# MegaPlay_Hammond1593J.net
KiCad netlist of a schematic drawn in EAGLE
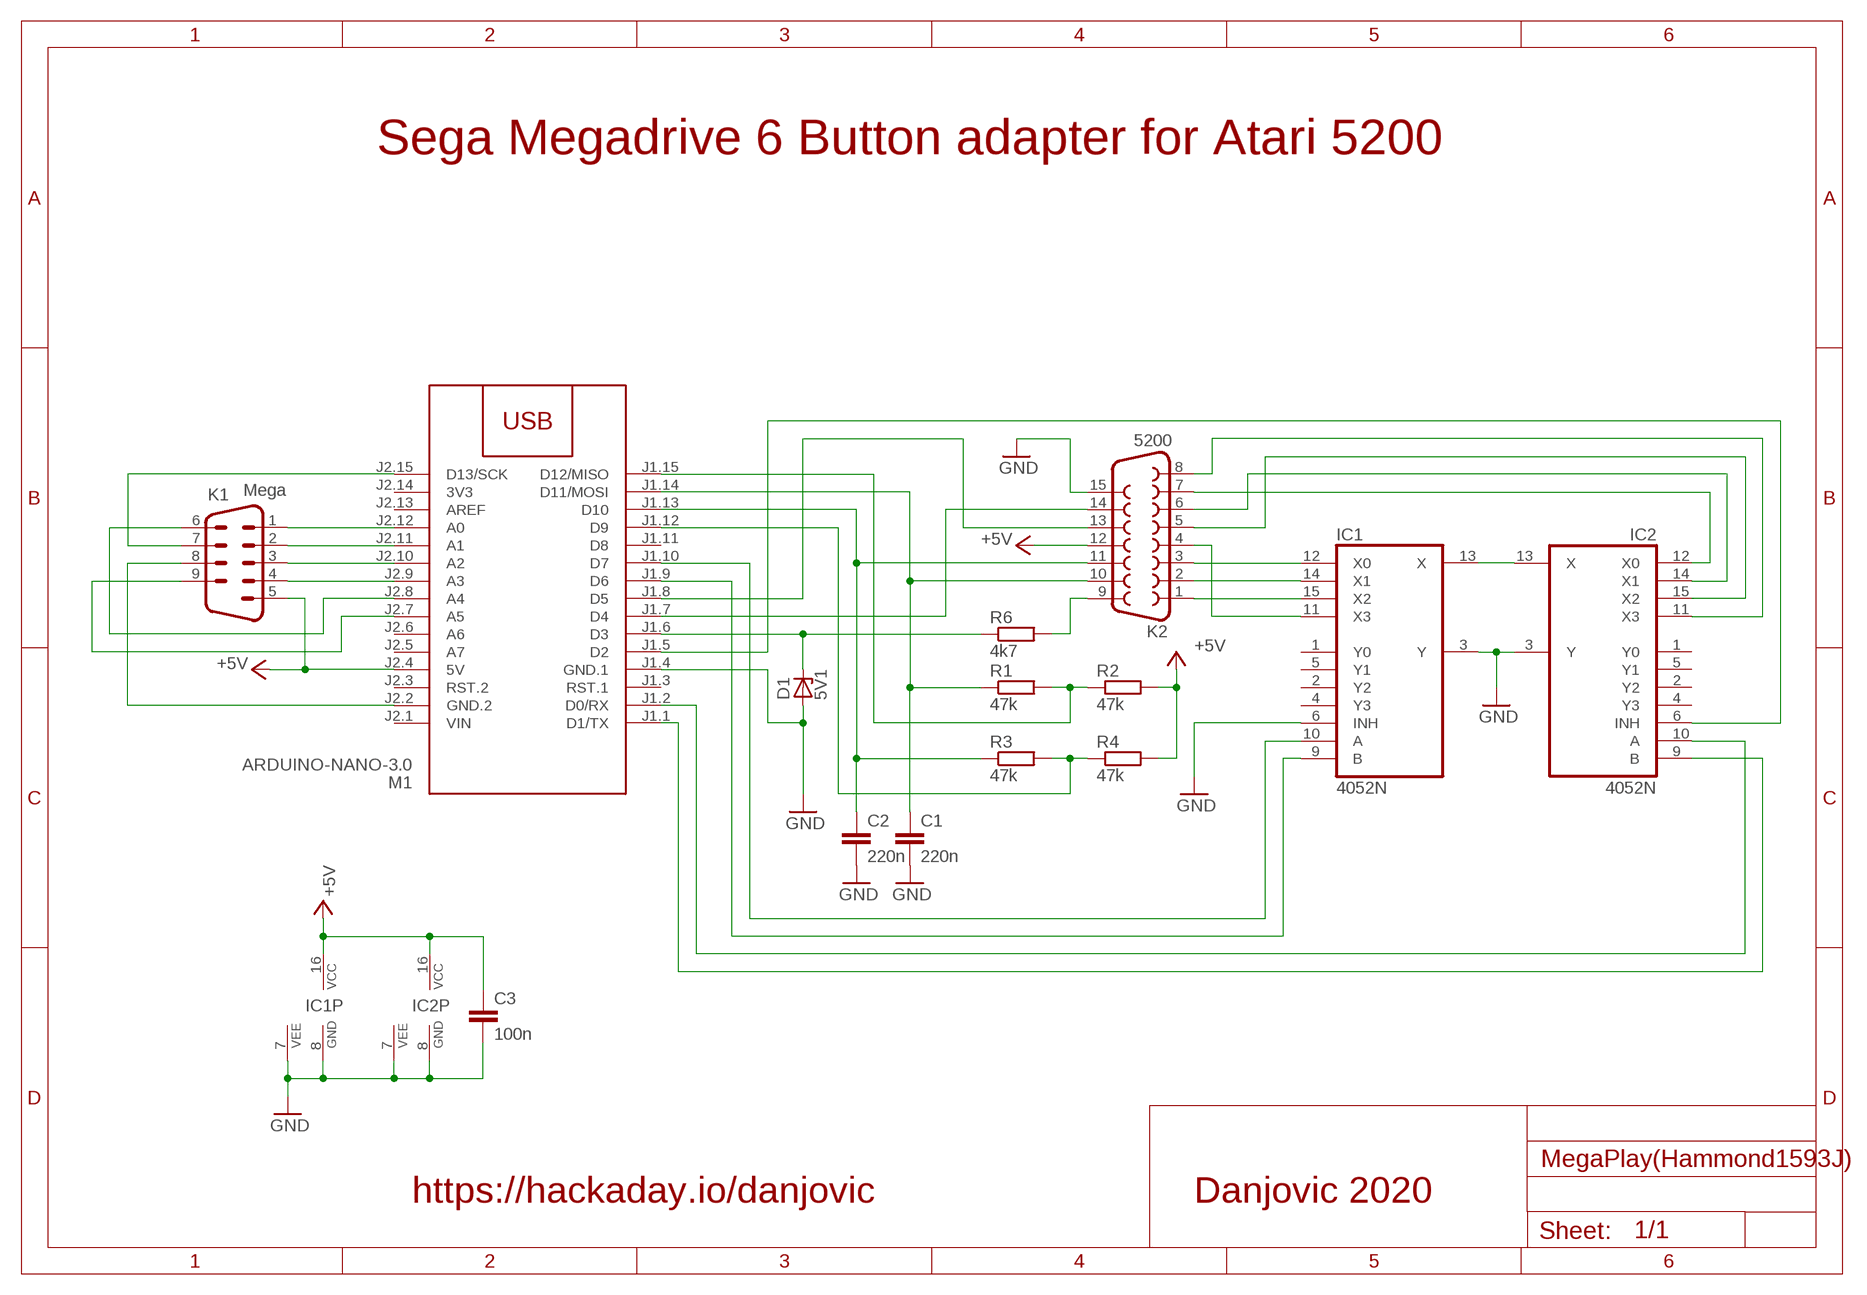
[diagram p0: schematic, sheet 1]

(export (version "E")
  (design (tool "Eeschema 10.0.6"))
  (components
    (comp (ref "C1")
      (value "220n")
      (footprint "eagle-import:C050-025X075")
      (libsource (lib "eagle-import") (part "C-EU050-025X075"))
    )
    (comp (ref "C2")
      (value "220n")
      (footprint "eagle-import:C050-025X075")
      (libsource (lib "eagle-import") (part "C-EU050-025X075"))
    )
    (comp (ref "C3")
      (value "100n")
      (footprint "eagle-import:C050-024X044")
      (libsource (lib "eagle-import") (part "C-EU050-024X044"))
    )
    (comp (ref "D1")
      (value "5V1")
      (footprint "eagle-import:ZDIO-7.5")
      (libsource (lib "eagle-import") (part "ZENER-DIODEZD-7.5"))
    )
    (comp (ref "IC1")
      (value "4052N")
      (footprint "eagle-import:DIL16")
      (libsource (lib "eagle-import") (part "4052N"))
    )
    (comp (ref "IC2")
      (value "4052N")
      (footprint "eagle-import:DIL16")
      (libsource (lib "eagle-import") (part "4052N"))
    )
    (comp (ref "K1")
      (value "Mega")
      (footprint "eagle-import:M09H")
      (libsource (lib "eagle-import") (part "M09H"))
    )
    (comp (ref "K2")
      (value "5200")
      (footprint "eagle-import:F15H")
      (libsource (lib "eagle-import") (part "F15H"))
    )
    (comp (ref "M1")
      (value "ARDUINO-NANO-3.0")
      (footprint "eagle-import:ARDUINO-NANO-3.0")
      (libsource (lib "eagle-import") (part "ARDUINO-NANO-3.0"))
    )
    (comp (ref "R1")
      (value "47k")
      (footprint "eagle-import:0204_7")
      (libsource (lib "eagle-import") (part "R-EU_0204/7"))
    )
    (comp (ref "R2")
      (value "47k")
      (footprint "eagle-import:0204_7")
      (libsource (lib "eagle-import") (part "R-EU_0204/7"))
    )
    (comp (ref "R3")
      (value "47k")
      (footprint "eagle-import:0204_7")
      (libsource (lib "eagle-import") (part "R-EU_0204/7"))
    )
    (comp (ref "R4")
      (value "47k")
      (footprint "eagle-import:0204_7")
      (libsource (lib "eagle-import") (part "R-EU_0204/7"))
    )
    (comp (ref "R6")
      (value "4k7")
      (footprint "eagle-import:0204_7")
      (libsource (lib "eagle-import") (part "R-EU_0204/7"))
    )
  )
  (nets
    (net (code "1") (name "+5V") (class "Default")
      (node (ref "C3") (pin "1") (pinfunction "1_1") (pintype "passive"))
      (node (ref "IC1") (pin "16") (pinfunction "VCC_16") (pintype "power_in"))
      (node (ref "IC2") (pin "16") (pinfunction "VCC_16") (pintype "power_in"))
      (node (ref "K1") (pin "5") (pinfunction "5_5") (pintype "passive"))
      (node (ref "K2") (pin "12") (pinfunction "12_12") (pintype "passive"))
      (node (ref "M1") (pin "J2.4") (pinfunction "5V_J2.4") (pintype "power_in"))
      (node (ref "R2") (pin "2") (pinfunction "2_2") (pintype "passive"))
      (node (ref "R4") (pin "2") (pinfunction "2_2") (pintype "passive"))
    )
    (net (code "2") (name "/3V3") (class "Default")
      (node (ref "M1") (pin "J2.14") (pinfunction "3V3_J2.14") (pintype "power_in"))
    )
    (net (code "3") (name "/VIN") (class "Default")
      (node (ref "M1") (pin "J2.1") (pinfunction "VIN_J2.1") (pintype "power_in"))
    )
    (net (code "4") (name "GND") (class "Default")
      (node (ref "C1") (pin "2") (pinfunction "2_2") (pintype "passive"))
      (node (ref "C2") (pin "2") (pinfunction "2_2") (pintype "passive"))
      (node (ref "C3") (pin "2") (pinfunction "2_2") (pintype "passive"))
      (node (ref "D1") (pin "A") (pinfunction "A_A") (pintype "passive"))
      (node (ref "IC1") (pin "3") (pinfunction "Y_3") (pintype "bidirectional"))
      (node (ref "IC1") (pin "6") (pinfunction "INH_6") (pintype "input"))
      (node (ref "IC1") (pin "7") (pinfunction "VEE_7") (pintype "power_in"))
      (node (ref "IC1") (pin "8") (pinfunction "GND_8") (pintype "power_in"))
      (node (ref "IC2") (pin "3") (pinfunction "Y_3") (pintype "bidirectional"))
      (node (ref "IC2") (pin "7") (pinfunction "VEE_7") (pintype "power_in"))
      (node (ref "IC2") (pin "8") (pinfunction "GND_8") (pintype "power_in"))
      (node (ref "K2") (pin "15") (pinfunction "15_15") (pintype "passive"))
      (node (ref "M1") (pin "J1.4") (pinfunction "GND.1_J1.4") (pintype "power_in"))
    )
    (net (code "5") (name "Net-(IC1A-A)") (class "Default")
      (node (ref "IC1") (pin "10") (pinfunction "A_10") (pintype "input"))
      (node (ref "M1") (pin "J1.10") (pinfunction "D7_J1.10") (pintype "bidirectional"))
    )
    (net (code "6") (name "Net-(IC1A-B)") (class "Default")
      (node (ref "IC1") (pin "9") (pinfunction "B_9") (pintype "input"))
      (node (ref "M1") (pin "J1.9") (pinfunction "D6_J1.9") (pintype "bidirectional"))
    )
    (net (code "7") (name "Net-(IC1A-X)") (class "Default")
      (node (ref "IC1") (pin "13") (pinfunction "X_13") (pintype "bidirectional"))
      (node (ref "IC2") (pin "13") (pinfunction "X_13") (pintype "bidirectional"))
    )
    (net (code "8") (name "Net-(IC1A-X0)") (class "Default")
      (node (ref "IC1") (pin "12") (pinfunction "X0_12") (pintype "bidirectional"))
      (node (ref "K2") (pin "3") (pinfunction "3_3") (pintype "passive"))
    )
    (net (code "9") (name "Net-(IC1A-X1)") (class "Default")
      (node (ref "IC1") (pin "14") (pinfunction "X1_14") (pintype "bidirectional"))
      (node (ref "K2") (pin "2") (pinfunction "2_2") (pintype "passive"))
    )
    (net (code "10") (name "Net-(IC1A-X2)") (class "Default")
      (node (ref "IC1") (pin "15") (pinfunction "X2_15") (pintype "bidirectional"))
      (node (ref "K2") (pin "1") (pinfunction "1_1") (pintype "passive"))
    )
    (net (code "11") (name "Net-(IC1A-X3)") (class "Default")
      (node (ref "IC1") (pin "11") (pinfunction "X3_11") (pintype "bidirectional"))
      (node (ref "K2") (pin "4") (pinfunction "4_4") (pintype "passive"))
    )
    (net (code "12") (name "Net-(IC2A-A)") (class "Default")
      (node (ref "IC2") (pin "10") (pinfunction "A_10") (pintype "input"))
      (node (ref "M1") (pin "J1.2") (pinfunction "D0/RX_J1.2") (pintype "bidirectional"))
    )
    (net (code "13") (name "Net-(IC2A-B)") (class "Default")
      (node (ref "IC2") (pin "9") (pinfunction "B_9") (pintype "input"))
      (node (ref "M1") (pin "J1.1") (pinfunction "D1/TX_J1.1") (pintype "bidirectional"))
    )
    (net (code "14") (name "Net-(IC2A-INH)") (class "Default")
      (node (ref "IC2") (pin "6") (pinfunction "INH_6") (pintype "input"))
      (node (ref "M1") (pin "J1.5") (pinfunction "D2_J1.5") (pintype "bidirectional"))
    )
    (net (code "15") (name "Net-(IC2A-X0)") (class "Default")
      (node (ref "IC2") (pin "12") (pinfunction "X0_12") (pintype "bidirectional"))
      (node (ref "K2") (pin "7") (pinfunction "7_7") (pintype "passive"))
    )
    (net (code "16") (name "Net-(IC2A-X1)") (class "Default")
      (node (ref "IC2") (pin "14") (pinfunction "X1_14") (pintype "bidirectional"))
      (node (ref "K2") (pin "6") (pinfunction "6_6") (pintype "passive"))
    )
    (net (code "17") (name "Net-(IC2A-X2)") (class "Default")
      (node (ref "IC2") (pin "15") (pinfunction "X2_15") (pintype "bidirectional"))
      (node (ref "K2") (pin "5") (pinfunction "5_5") (pintype "passive"))
    )
    (net (code "18") (name "Net-(IC2A-X3)") (class "Default")
      (node (ref "IC2") (pin "11") (pinfunction "X3_11") (pintype "bidirectional"))
      (node (ref "K2") (pin "8") (pinfunction "8_8") (pintype "passive"))
    )
    (net (code "19") (name "Net-(K2-Pad9)") (class "Default")
      (node (ref "K2") (pin "9") (pinfunction "9_9") (pintype "passive"))
      (node (ref "R6") (pin "2") (pinfunction "2_2") (pintype "passive"))
    )
    (net (code "20") (name "Net-(M1-A0)") (class "Default")
      (node (ref "K1") (pin "1") (pinfunction "1_1") (pintype "passive"))
      (node (ref "M1") (pin "J2.12") (pinfunction "A0_J2.12") (pintype "bidirectional"))
    )
    (net (code "21") (name "Net-(M1-A1)") (class "Default")
      (node (ref "K1") (pin "2") (pinfunction "2_2") (pintype "passive"))
      (node (ref "M1") (pin "J2.11") (pinfunction "A1_J2.11") (pintype "bidirectional"))
    )
    (net (code "22") (name "Net-(M1-A2)") (class "Default")
      (node (ref "K1") (pin "3") (pinfunction "3_3") (pintype "passive"))
      (node (ref "M1") (pin "J2.10") (pinfunction "A2_J2.10") (pintype "bidirectional"))
    )
    (net (code "23") (name "Net-(M1-A3)") (class "Default")
      (node (ref "K1") (pin "4") (pinfunction "4_4") (pintype "passive"))
      (node (ref "M1") (pin "J2.9") (pinfunction "A3_J2.9") (pintype "bidirectional"))
    )
    (net (code "24") (name "Net-(M1-A4)") (class "Default")
      (node (ref "K1") (pin "6") (pinfunction "6_6") (pintype "passive"))
      (node (ref "M1") (pin "J2.8") (pinfunction "A4_J2.8") (pintype "bidirectional"))
    )
    (net (code "25") (name "Net-(M1-A5)") (class "Default")
      (node (ref "K1") (pin "9") (pinfunction "9_9") (pintype "passive"))
      (node (ref "M1") (pin "J2.7") (pinfunction "A5_J2.7") (pintype "bidirectional"))
    )
    (net (code "26") (name "Net-(M1-D3)") (class "Default")
      (node (ref "D1") (pin "C") (pinfunction "C_C") (pintype "passive"))
      (node (ref "M1") (pin "J1.6") (pinfunction "D3_J1.6") (pintype "bidirectional"))
      (node (ref "R6") (pin "1") (pinfunction "1_1") (pintype "passive"))
    )
    (net (code "27") (name "Net-(M1-D4)") (class "Default")
      (node (ref "K2") (pin "14") (pinfunction "14_14") (pintype "passive"))
      (node (ref "M1") (pin "J1.7") (pinfunction "D4_J1.7") (pintype "bidirectional"))
    )
    (net (code "28") (name "Net-(M1-D5)") (class "Default")
      (node (ref "K2") (pin "13") (pinfunction "13_13") (pintype "passive"))
      (node (ref "M1") (pin "J1.8") (pinfunction "D5_J1.8") (pintype "bidirectional"))
    )
    (net (code "29") (name "Net-(M1-D9)") (class "Default")
      (node (ref "M1") (pin "J1.12") (pinfunction "D9_J1.12") (pintype "bidirectional"))
      (node (ref "R3") (pin "2") (pinfunction "2_2") (pintype "passive"))
      (node (ref "R4") (pin "1") (pinfunction "1_1") (pintype "passive"))
    )
    (net (code "30") (name "Net-(M1-D10)") (class "Default")
      (node (ref "C2") (pin "1") (pinfunction "1_1") (pintype "passive"))
      (node (ref "K2") (pin "11") (pinfunction "11_11") (pintype "passive"))
      (node (ref "M1") (pin "J1.13") (pinfunction "D10_J1.13") (pintype "bidirectional"))
      (node (ref "R3") (pin "1") (pinfunction "1_1") (pintype "passive"))
    )
    (net (code "31") (name "Net-(M1-D11{slash}MOSI)") (class "Default")
      (node (ref "C1") (pin "1") (pinfunction "1_1") (pintype "passive"))
      (node (ref "K2") (pin "10") (pinfunction "10_10") (pintype "passive"))
      (node (ref "M1") (pin "J1.14") (pinfunction "D11/MOSI_J1.14") (pintype "bidirectional"))
      (node (ref "R1") (pin "1") (pinfunction "1_1") (pintype "passive"))
    )
    (net (code "32") (name "Net-(M1-D12{slash}MISO)") (class "Default")
      (node (ref "M1") (pin "J1.15") (pinfunction "D12/MISO_J1.15") (pintype "bidirectional"))
      (node (ref "R1") (pin "2") (pinfunction "2_2") (pintype "passive"))
      (node (ref "R2") (pin "1") (pinfunction "1_1") (pintype "passive"))
    )
    (net (code "33") (name "Net-(M1-D13{slash}SCK)") (class "Default")
      (node (ref "K1") (pin "7") (pinfunction "7_7") (pintype "passive"))
      (node (ref "M1") (pin "J2.15") (pinfunction "D13/SCK_J2.15") (pintype "bidirectional"))
    )
    (net (code "34") (name "Net-(M1-GND.2)") (class "Default")
      (node (ref "K1") (pin "8") (pinfunction "8_8") (pintype "passive"))
      (node (ref "M1") (pin "J2.2") (pinfunction "GND.2_J2.2") (pintype "power_in"))
    )
    (net (code "35") (name "unconnected-(IC1A-Y0-Pad1)") (class "Default")
      (node (ref "IC1") (pin "1") (pinfunction "Y0_1") (pintype "bidirectional"))
    )
    (net (code "36") (name "unconnected-(IC1A-Y1-Pad5)") (class "Default")
      (node (ref "IC1") (pin "5") (pinfunction "Y1_5") (pintype "bidirectional"))
    )
    (net (code "37") (name "unconnected-(IC1A-Y2-Pad2)") (class "Default")
      (node (ref "IC1") (pin "2") (pinfunction "Y2_2") (pintype "bidirectional"))
    )
    (net (code "38") (name "unconnected-(IC1A-Y3-Pad4)") (class "Default")
      (node (ref "IC1") (pin "4") (pinfunction "Y3_4") (pintype "bidirectional"))
    )
    (net (code "39") (name "unconnected-(IC2A-Y0-Pad1)") (class "Default")
      (node (ref "IC2") (pin "1") (pinfunction "Y0_1") (pintype "bidirectional"))
    )
    (net (code "40") (name "unconnected-(IC2A-Y1-Pad5)") (class "Default")
      (node (ref "IC2") (pin "5") (pinfunction "Y1_5") (pintype "bidirectional"))
    )
    (net (code "41") (name "unconnected-(IC2A-Y2-Pad2)") (class "Default")
      (node (ref "IC2") (pin "2") (pinfunction "Y2_2") (pintype "bidirectional"))
    )
    (net (code "42") (name "unconnected-(IC2A-Y3-Pad4)") (class "Default")
      (node (ref "IC2") (pin "4") (pinfunction "Y3_4") (pintype "bidirectional"))
    )
    (net (code "43") (name "unconnected-(M1-A6-PadJ2.6)") (class "Default")
      (node (ref "M1") (pin "J2.6") (pinfunction "A6_J2.6") (pintype "bidirectional"))
    )
    (net (code "44") (name "unconnected-(M1-A7-PadJ2.5)") (class "Default")
      (node (ref "M1") (pin "J2.5") (pinfunction "A7_J2.5") (pintype "bidirectional"))
    )
    (net (code "45") (name "unconnected-(M1-AREF-PadJ2.13)") (class "Default")
      (node (ref "M1") (pin "J2.13") (pinfunction "AREF_J2.13") (pintype "bidirectional"))
    )
    (net (code "46") (name "unconnected-(M1-D8-PadJ1.11)") (class "Default")
      (node (ref "M1") (pin "J1.11") (pinfunction "D8_J1.11") (pintype "bidirectional"))
    )
    (net (code "47") (name "unconnected-(M1-RST.1-PadJ1.3)") (class "Default")
      (node (ref "M1") (pin "J1.3") (pinfunction "RST.1_J1.3") (pintype "bidirectional"))
    )
    (net (code "48") (name "unconnected-(M1-RST.2-PadJ2.3)") (class "Default")
      (node (ref "M1") (pin "J2.3") (pinfunction "RST.2_J2.3") (pintype "bidirectional"))
    )
  )
)
